# board.net
KiCad netlist of a schematic drawn in EAGLE
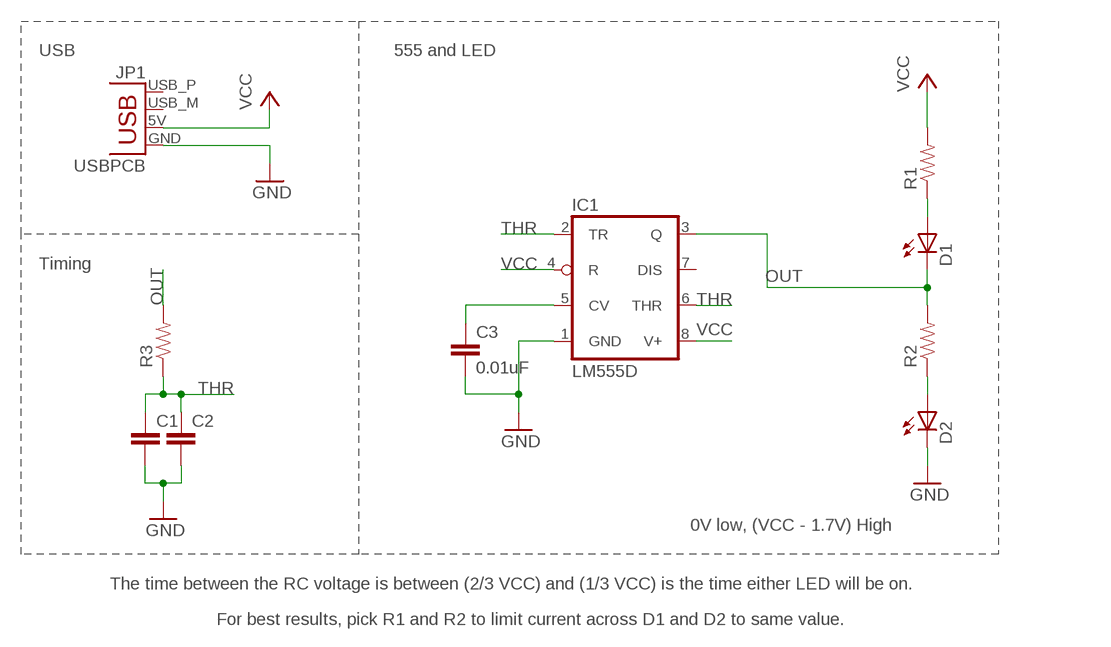
[diagram p0: schematic, sheet 1]

(export (version "E")
  (design (tool "Eeschema 10.0.6"))
  (components
    (comp (ref "C1")
      (value "CAP0805")
      (footprint "eagle-import:0805")
      (libsource (lib "eagle-import") (part "CAP0805"))
    )
    (comp (ref "C2")
      (value "CAP0805")
      (footprint "eagle-import:0805")
      (libsource (lib "eagle-import") (part "CAP0805"))
    )
    (comp (ref "C3")
      (value "0.01uF")
      (footprint "eagle-import:0805")
      (libsource (lib "eagle-import") (part "CAP0805"))
    )
    (comp (ref "D1")
      (value "LEDCHIP-LED0805")
      (footprint "eagle-import:CHIP-LED0805")
      (libsource (lib "eagle-import") (part "LEDCHIP-LED0805"))
    )
    (comp (ref "D2")
      (value "LEDCHIP-LED0805")
      (footprint "eagle-import:CHIP-LED0805")
      (libsource (lib "eagle-import") (part "LEDCHIP-LED0805"))
    )
    (comp (ref "IC1")
      (value "LM555D")
      (footprint "eagle-import:SO08")
      (libsource (lib "eagle-import") (part "555DLM"))
    )
    (comp (ref "JP1")
      (value "USBPCB")
      (footprint "eagle-import:USB-A-PCB")
      (libsource (lib "eagle-import") (part "USBPCB"))
    )
    (comp (ref "R1")
      (value "RESISTOR0805-RES")
      (footprint "eagle-import:0805")
      (libsource (lib "eagle-import") (part "RESISTOR0805-RES"))
    )
    (comp (ref "R2")
      (value "RESISTOR0805-RES")
      (footprint "eagle-import:0805")
      (libsource (lib "eagle-import") (part "RESISTOR0805-RES"))
    )
    (comp (ref "R3")
      (value "RESISTOR0805-RES")
      (footprint "eagle-import:0805")
      (libsource (lib "eagle-import") (part "RESISTOR0805-RES"))
    )
  )
  (nets
    (net (code "1") (name "/OUT") (class "Default")
      (node (ref "D1") (pin "C") (pinfunction "C_C") (pintype "passive"))
      (node (ref "IC1") (pin "3") (pinfunction "Q_3") (pintype "output"))
      (node (ref "R2") (pin "2") (pinfunction "2_2") (pintype "passive"))
      (node (ref "R3") (pin "2") (pinfunction "2_2") (pintype "passive"))
    )
    (net (code "2") (name "/THR") (class "Default")
      (node (ref "C1") (pin "1") (pinfunction "1_1") (pintype "passive"))
      (node (ref "C2") (pin "1") (pinfunction "1_1") (pintype "passive"))
      (node (ref "IC1") (pin "2") (pinfunction "TR_2") (pintype "input"))
      (node (ref "IC1") (pin "6") (pinfunction "THR_6") (pintype "input"))
      (node (ref "R3") (pin "1") (pinfunction "1_1") (pintype "passive"))
    )
    (net (code "3") (name "GND") (class "Default")
      (node (ref "C1") (pin "2") (pinfunction "2_2") (pintype "passive"))
      (node (ref "C2") (pin "2") (pinfunction "2_2") (pintype "passive"))
      (node (ref "C3") (pin "2") (pinfunction "2_2") (pintype "passive"))
      (node (ref "D2") (pin "C") (pinfunction "C_C") (pintype "passive"))
      (node (ref "IC1") (pin "1") (pinfunction "GND_1") (pintype "power_in"))
      (node (ref "JP1") (pin "GND") (pinfunction "GND_GND") (pintype "bidirectional"))
    )
    (net (code "4") (name "Net-(D1-PadA)") (class "Default")
      (node (ref "D1") (pin "A") (pinfunction "A_A") (pintype "passive"))
      (node (ref "R1") (pin "1") (pinfunction "1_1") (pintype "passive"))
    )
    (net (code "5") (name "Net-(D2-PadA)") (class "Default")
      (node (ref "D2") (pin "A") (pinfunction "A_A") (pintype "passive"))
      (node (ref "R2") (pin "1") (pinfunction "1_1") (pintype "passive"))
    )
    (net (code "6") (name "Net-(IC1-CV)") (class "Default")
      (node (ref "C3") (pin "1") (pinfunction "1_1") (pintype "passive"))
      (node (ref "IC1") (pin "5") (pinfunction "CV_5") (pintype "input"))
    )
    (net (code "7") (name "VCC") (class "Default")
      (node (ref "IC1") (pin "4") (pinfunction "R_4") (pintype "input"))
      (node (ref "IC1") (pin "8") (pinfunction "V+_8") (pintype "power_in"))
      (node (ref "JP1") (pin "5V") (pinfunction "VBUS_5V") (pintype "bidirectional"))
      (node (ref "R1") (pin "2") (pinfunction "2_2") (pintype "passive"))
    )
    (net (code "8") (name "unconnected-(IC1-DIS-Pad7)") (class "Default")
      (node (ref "IC1") (pin "7") (pinfunction "DIS_7") (pintype "input"))
    )
    (net (code "9") (name "unconnected-(JP1-D+-PadUSB_P)") (class "Default")
      (node (ref "JP1") (pin "USB_P") (pinfunction "D+_USB_P") (pintype "bidirectional"))
    )
    (net (code "10") (name "unconnected-(JP1-D--PadUSB_M)") (class "Default")
      (node (ref "JP1") (pin "USB_M") (pinfunction "D-_USB_M") (pintype "bidirectional"))
    )
  )
)
